# ultimatedrive2.net
KiCad netlist of a schematic drawn in EAGLE
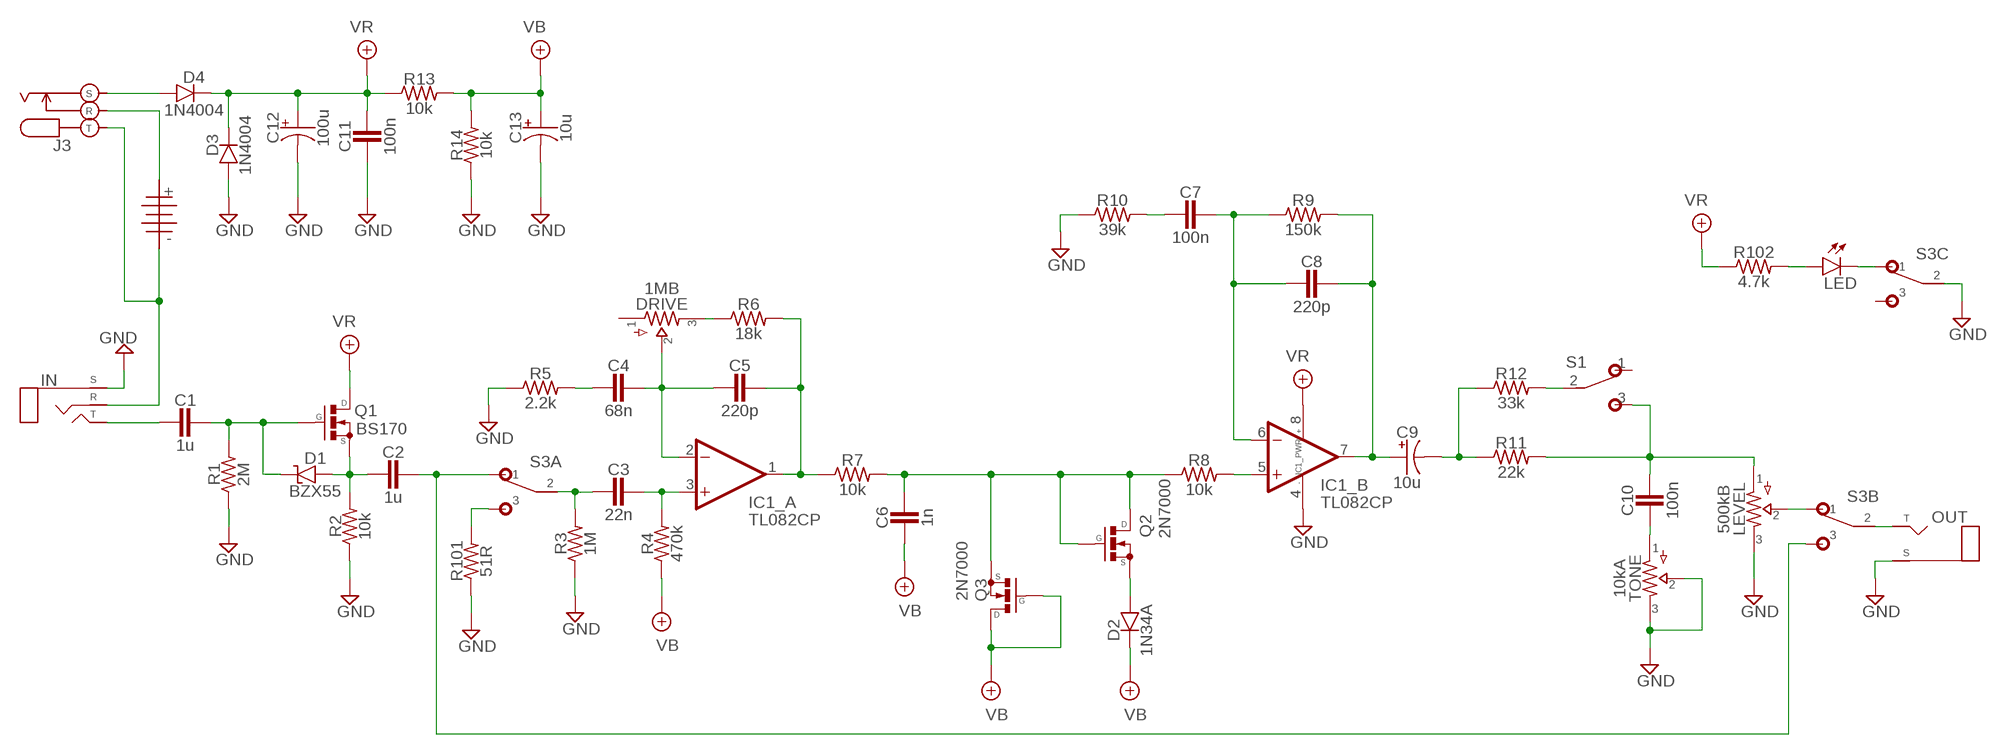
[diagram p0: schematic, sheet 1]

(export (version "E")
  (design (tool "Eeschema 10.0.6"))
  (components
    (comp (ref "1")
      (value "BATTERY")
      (footprint "eagle-import:TWO_PADS")
      (libsource (lib "eagle-import") (part "BATTERY"))
    )
    (comp (ref "C1")
      (value "1u")
      (footprint "eagle-import:BOX_SMALL")
      (libsource (lib "eagle-import") (part "CER/FILMBOX.1"))
    )
    (comp (ref "C2")
      (value "1u")
      (footprint "eagle-import:BOX_SMALL")
      (libsource (lib "eagle-import") (part "CER/FILMBOX.1"))
    )
    (comp (ref "C3")
      (value "22n")
      (footprint "eagle-import:BOX_SMALL")
      (libsource (lib "eagle-import") (part "CER/FILMBOX.1"))
    )
    (comp (ref "C4")
      (value "68n")
      (footprint "eagle-import:BOX_SMALL")
      (libsource (lib "eagle-import") (part "CER/FILMBOX.1"))
    )
    (comp (ref "C5")
      (value "220p")
      (footprint "eagle-import:BOX_SMALL")
      (libsource (lib "eagle-import") (part "CER/FILMBOX.1"))
    )
    (comp (ref "C6")
      (value "1n")
      (footprint "eagle-import:BOX_SMALL")
      (libsource (lib "eagle-import") (part "CER/FILMBOX.1"))
    )
    (comp (ref "C7")
      (value "100n")
      (footprint "eagle-import:BOX_SMALL")
      (libsource (lib "eagle-import") (part "CER/FILMBOX.1"))
    )
    (comp (ref "C8")
      (value "220p")
      (footprint "eagle-import:BOX_SMALL")
      (libsource (lib "eagle-import") (part "CER/FILMBOX.1"))
    )
    (comp (ref "C9")
      (value "10u")
      (footprint "eagle-import:050_020")
      (libsource (lib "eagle-import") (part "0500"))
    )
    (comp (ref "C10")
      (value "100n")
      (footprint "eagle-import:BOX_SMALL")
      (libsource (lib "eagle-import") (part "CER/FILMBOX.1"))
    )
    (comp (ref "C11")
      (value "100n")
      (footprint "eagle-import:BOX_SMALL")
      (libsource (lib "eagle-import") (part "CER/FILMBOX.1"))
    )
    (comp (ref "C12")
      (value "100u")
      (footprint "eagle-import:050_020")
      (libsource (lib "eagle-import") (part "0500"))
    )
    (comp (ref "C13")
      (value "10u")
      (footprint "eagle-import:050_020")
      (libsource (lib "eagle-import") (part "0500"))
    )
    (comp (ref "D1")
      (value "BZX55")
      (footprint "eagle-import:DO41-3")
      (libsource (lib "eagle-import") (part "ZENER.3"))
    )
    (comp (ref "D2")
      (value "1N34A")
      (footprint "eagle-import:DO41-2")
      (libsource (lib "eagle-import") (part "DO41.2"))
    )
    (comp (ref "D3")
      (value "1N4004")
      (footprint "eagle-import:DO41-3")
      (libsource (lib "eagle-import") (part "DO41.3"))
    )
    (comp (ref "D4")
      (value "1N4004")
      (footprint "eagle-import:DO41-3")
      (libsource (lib "eagle-import") (part "DO41.3"))
    )
    (comp (ref "DRIVE")
      (value "1MB")
      (footprint "eagle-import:16MM")
      (libsource (lib "eagle-import") (part "POTS16MM"))
    )
    (comp (ref "IC1")
      (value "TL082CP")
      (footprint "eagle-import:DIL0")
      (libsource (lib "eagle-import") (part "DUALTH"))
    )
    (comp (ref "IN")
      (value "STEREO")
      (footprint "eagle-import:STEREO_PCB")
      (libsource (lib "eagle-import") (part "STEREO"))
    )
    (comp (ref "J3")
      (value "DC_KOBICONN")
      (footprint "eagle-import:DC_KOBICONN")
      (libsource (lib "eagle-import") (part "DC_KOBICONN"))
    )
    (comp (ref "LED")
      (value "LED")
      (footprint "eagle-import:3MM_D")
      (libsource (lib "eagle-import") (part "LED"))
    )
    (comp (ref "LEVEL")
      (value "500kB")
      (footprint "eagle-import:16MM")
      (libsource (lib "eagle-import") (part "POTS16MM"))
    )
    (comp (ref "OUT")
      (value "MONO")
      (footprint "eagle-import:TWO_PADS")
      (libsource (lib "eagle-import") (part "MONO"))
    )
    (comp (ref "Q1")
      (value "BS170")
      (footprint "eagle-import:SOT54ES")
      (libsource (lib "eagle-import") (part "BS170"))
    )
    (comp (ref "Q2")
      (value "2N7000")
      (footprint "eagle-import:TO92-")
      (libsource (lib "eagle-import") (part "2N7000"))
    )
    (comp (ref "Q3")
      (value "2N7000")
      (footprint "eagle-import:TO92-")
      (libsource (lib "eagle-import") (part "2N7000"))
    )
    (comp (ref "R1")
      (value "2M")
      (footprint "eagle-import:R0207_3")
      (libsource (lib "eagle-import") (part "R_.3B"))
    )
    (comp (ref "R2")
      (value "10k")
      (footprint "eagle-import:R0207_3")
      (libsource (lib "eagle-import") (part "R_.3B"))
    )
    (comp (ref "R3")
      (value "1M")
      (footprint "eagle-import:R0207_3")
      (libsource (lib "eagle-import") (part "R_.3B"))
    )
    (comp (ref "R4")
      (value "470k")
      (footprint "eagle-import:R0207_3")
      (libsource (lib "eagle-import") (part "R_.3B"))
    )
    (comp (ref "R5")
      (value "2.2k")
      (footprint "eagle-import:R0207_3")
      (libsource (lib "eagle-import") (part "R_.3B"))
    )
    (comp (ref "R6")
      (value "18k")
      (footprint "eagle-import:R0207_3")
      (libsource (lib "eagle-import") (part "R_.3B"))
    )
    (comp (ref "R7")
      (value "10k")
      (footprint "eagle-import:R0207_3")
      (libsource (lib "eagle-import") (part "R_.3B"))
    )
    (comp (ref "R8")
      (value "10k")
      (footprint "eagle-import:R0207_3")
      (libsource (lib "eagle-import") (part "R_.3B"))
    )
    (comp (ref "R9")
      (value "150k")
      (footprint "eagle-import:R0207_3")
      (libsource (lib "eagle-import") (part "R_.3B"))
    )
    (comp (ref "R10")
      (value "39k")
      (footprint "eagle-import:R0207_3")
      (libsource (lib "eagle-import") (part "R_.3B"))
    )
    (comp (ref "R11")
      (value "22k")
      (footprint "eagle-import:R0207_3")
      (libsource (lib "eagle-import") (part "R_.3B"))
    )
    (comp (ref "R12")
      (value "33k")
      (footprint "eagle-import:R0207_3")
      (libsource (lib "eagle-import") (part "R_.3B"))
    )
    (comp (ref "R13")
      (value "10k")
      (footprint "eagle-import:R0207_3")
      (libsource (lib "eagle-import") (part "R_.3B"))
    )
    (comp (ref "R14")
      (value "10k")
      (footprint "eagle-import:R0207_3")
      (libsource (lib "eagle-import") (part "R_.3B"))
    )
    (comp (ref "R101")
      (value "51R")
      (footprint "eagle-import:R0207_3")
      (libsource (lib "eagle-import") (part "R_.3B"))
    )
    (comp (ref "R102")
      (value "4.7k")
      (footprint "eagle-import:R0207_3")
      (libsource (lib "eagle-import") (part "R_.3B"))
    )
    (comp (ref "S1")
      (value "SPDT")
      (footprint "eagle-import:M9040P")
      (libsource (lib "eagle-import") (part "SPDT"))
    )
    (comp (ref "S3")
      (value "3PDT")
      (footprint "eagle-import:3PDT")
      (libsource (lib "eagle-import") (part "3PDT"))
    )
    (comp (ref "TONE")
      (value "10kA")
      (footprint "eagle-import:16MM")
      (libsource (lib "eagle-import") (part "POTS16MM"))
    )
  )
  (nets
    (net (code "1") (name "GND") (class "Default")
      (node (ref "C11") (pin "2") (pinfunction "2_2") (pintype "passive"))
      (node (ref "C12") (pin "-") (pinfunction "-_-") (pintype "passive"))
      (node (ref "C13") (pin "-") (pinfunction "-_-") (pintype "passive"))
      (node (ref "D3") (pin "A") (pinfunction "A_A") (pintype "passive"))
      (node (ref "IC1") (pin "4") (pinfunction "V-_4") (pintype "power_in"))
      (node (ref "IN") (pin "P$1") (pinfunction "S_P$1") (pintype "passive"))
      (node (ref "LEVEL") (pin "3") (pinfunction "3_3") (pintype "passive"))
      (node (ref "OUT") (pin "S") (pinfunction "SLEEVE_S") (pintype "passive"))
      (node (ref "R1") (pin "1") (pinfunction "1_1") (pintype "passive"))
      (node (ref "R10") (pin "1") (pinfunction "1_1") (pintype "passive"))
      (node (ref "R101") (pin "1") (pinfunction "1_1") (pintype "passive"))
      (node (ref "R14") (pin "1") (pinfunction "1_1") (pintype "passive"))
      (node (ref "R2") (pin "1") (pinfunction "1_1") (pintype "passive"))
      (node (ref "R3") (pin "1") (pinfunction "1_1") (pintype "passive"))
      (node (ref "R5") (pin "1") (pinfunction "1_1") (pintype "passive"))
      (node (ref "S3") (pin "C2") (pinfunction "2_C2") (pintype "passive"))
      (node (ref "TONE") (pin "2") (pinfunction "2_2") (pintype "passive"))
      (node (ref "TONE") (pin "3") (pinfunction "3_3") (pintype "passive"))
    )
    (net (code "2") (name "Net-(1-P$1)") (class "Default")
      (node (ref "1") (pin "T") (pinfunction "P$1_T") (pintype "bidirectional"))
      (node (ref "J3") (pin "R") (pinfunction "R_R") (pintype "bidirectional"))
    )
    (net (code "3") (name "Net-(1-P$2)") (class "Default")
      (node (ref "1") (pin "S") (pinfunction "P$2_S") (pintype "bidirectional"))
      (node (ref "IN") (pin "P$2") (pinfunction "R_P$2") (pintype "passive"))
      (node (ref "J3") (pin "T") (pinfunction "T_T") (pintype "bidirectional"))
    )
    (net (code "4") (name "Net-(C1-Pad1)") (class "Default")
      (node (ref "C1") (pin "1") (pinfunction "1_1") (pintype "passive"))
      (node (ref "D1") (pin "C") (pinfunction "C_C") (pintype "passive"))
      (node (ref "Q1") (pin "G") (pinfunction "G_G") (pintype "passive"))
      (node (ref "R1") (pin "2") (pinfunction "2_2") (pintype "passive"))
    )
    (net (code "5") (name "Net-(C2-Pad2)") (class "Default")
      (node (ref "C2") (pin "2") (pinfunction "2_2") (pintype "passive"))
      (node (ref "D1") (pin "A") (pinfunction "A_A") (pintype "passive"))
      (node (ref "Q1") (pin "S") (pinfunction "S_S") (pintype "passive"))
      (node (ref "R2") (pin "2") (pinfunction "2_2") (pintype "passive"))
    )
    (net (code "6") (name "Net-(C4-Pad2)") (class "Default")
      (node (ref "C4") (pin "2") (pinfunction "2_2") (pintype "passive"))
      (node (ref "R5") (pin "2") (pinfunction "2_2") (pintype "passive"))
    )
    (net (code "7") (name "Net-(C7-Pad2)") (class "Default")
      (node (ref "C7") (pin "2") (pinfunction "2_2") (pintype "passive"))
      (node (ref "R10") (pin "2") (pinfunction "2_2") (pintype "passive"))
    )
    (net (code "8") (name "Net-(C9-Pad-)") (class "Default")
      (node (ref "C9") (pin "-") (pinfunction "-_-") (pintype "passive"))
      (node (ref "R11") (pin "1") (pinfunction "1_1") (pintype "passive"))
      (node (ref "R12") (pin "1") (pinfunction "1_1") (pintype "passive"))
    )
    (net (code "9") (name "Net-(C10-Pad2)") (class "Default")
      (node (ref "C10") (pin "2") (pinfunction "2_2") (pintype "passive"))
      (node (ref "TONE") (pin "1") (pinfunction "1_1") (pintype "passive"))
    )
    (net (code "10") (name "Net-(D4-PadA)") (class "Default")
      (node (ref "D4") (pin "A") (pinfunction "A_A") (pintype "passive"))
      (node (ref "J3") (pin "S") (pinfunction "S_S") (pintype "bidirectional"))
    )
    (net (code "11") (name "Net-(DRIVE-Pad3)") (class "Default")
      (node (ref "DRIVE") (pin "3") (pinfunction "3_3") (pintype "passive"))
      (node (ref "R6") (pin "1") (pinfunction "1_1") (pintype "passive"))
    )
    (net (code "12") (name "Net-(IC1A-+IN)") (class "Default")
      (node (ref "C3") (pin "1") (pinfunction "1_1") (pintype "passive"))
      (node (ref "IC1") (pin "3") (pinfunction "+IN_3") (pintype "input"))
      (node (ref "R4") (pin "2") (pinfunction "2_2") (pintype "passive"))
    )
    (net (code "13") (name "Net-(IC1A--IN)") (class "Default")
      (node (ref "C4") (pin "1") (pinfunction "1_1") (pintype "passive"))
      (node (ref "C5") (pin "2") (pinfunction "2_2") (pintype "passive"))
      (node (ref "DRIVE") (pin "2") (pinfunction "2_2") (pintype "passive"))
      (node (ref "IC1") (pin "2") (pinfunction "-IN_2") (pintype "input"))
    )
    (net (code "14") (name "Net-(IC1A-OUT)") (class "Default")
      (node (ref "C5") (pin "1") (pinfunction "1_1") (pintype "passive"))
      (node (ref "IC1") (pin "1") (pinfunction "OUT_1") (pintype "output"))
      (node (ref "R6") (pin "2") (pinfunction "2_2") (pintype "passive"))
      (node (ref "R7") (pin "1") (pinfunction "1_1") (pintype "passive"))
    )
    (net (code "15") (name "Net-(IC1B-+IN)") (class "Default")
      (node (ref "IC1") (pin "5") (pinfunction "+IN_5") (pintype "input"))
      (node (ref "R8") (pin "2") (pinfunction "2_2") (pintype "passive"))
    )
    (net (code "16") (name "Net-(IC1B--IN)") (class "Default")
      (node (ref "C7") (pin "1") (pinfunction "1_1") (pintype "passive"))
      (node (ref "C8") (pin "2") (pinfunction "2_2") (pintype "passive"))
      (node (ref "IC1") (pin "6") (pinfunction "-IN_6") (pintype "input"))
      (node (ref "R9") (pin "1") (pinfunction "1_1") (pintype "passive"))
    )
    (net (code "17") (name "Net-(IC1B-OUT)") (class "Default")
      (node (ref "C8") (pin "1") (pinfunction "1_1") (pintype "passive"))
      (node (ref "C9") (pin "+") (pinfunction "+_+") (pintype "passive"))
      (node (ref "IC1") (pin "7") (pinfunction "OUT_7") (pintype "output"))
      (node (ref "R9") (pin "2") (pinfunction "2_2") (pintype "passive"))
    )
    (net (code "18") (name "Net-(IN-T)") (class "Default")
      (node (ref "C1") (pin "2") (pinfunction "2_2") (pintype "passive"))
      (node (ref "IN") (pin "P$3") (pinfunction "T_P$3") (pintype "passive"))
    )
    (net (code "19") (name "Net-(LED-A)") (class "Default")
      (node (ref "LED") (pin "ANODE") (pinfunction "A_ANODE") (pintype "passive"))
      (node (ref "R102") (pin "2") (pinfunction "2_2") (pintype "passive"))
    )
    (net (code "20") (name "Net-(LED-C)") (class "Default")
      (node (ref "LED") (pin "P$1") (pinfunction "C_P$1") (pintype "passive"))
      (node (ref "S3") (pin "C1") (pinfunction "1_C1") (pintype "passive"))
    )
    (net (code "21") (name "Net-(OUT-TIP)") (class "Default")
      (node (ref "OUT") (pin "T") (pinfunction "TIP_T") (pintype "passive"))
      (node (ref "S3") (pin "B2") (pinfunction "2_B2") (pintype "passive"))
    )
    (net (code "22") (name "Net-(Q2-D)") (class "Default")
      (node (ref "C6") (pin "1") (pinfunction "1_1") (pintype "passive"))
      (node (ref "Q2") (pin "1") (pinfunction "D_1") (pintype "passive"))
      (node (ref "Q2") (pin "2") (pinfunction "G_2") (pintype "passive"))
      (node (ref "Q3") (pin "3") (pinfunction "S_3") (pintype "passive"))
      (node (ref "R7") (pin "2") (pinfunction "2_2") (pintype "passive"))
      (node (ref "R8") (pin "1") (pinfunction "1_1") (pintype "passive"))
    )
    (net (code "23") (name "Net-(Q2-S)") (class "Default")
      (node (ref "D2") (pin "A") (pinfunction "A_A") (pintype "passive"))
      (node (ref "Q2") (pin "3") (pinfunction "S_3") (pintype "passive"))
    )
    (net (code "24") (name "Net-(S1-P)") (class "Default")
      (node (ref "R12") (pin "2") (pinfunction "2_2") (pintype "passive"))
      (node (ref "S1") (pin "2") (pinfunction "P_2") (pintype "passive"))
    )
    (net (code "25") (name "Net-(S1-S)") (class "Default")
      (node (ref "C10") (pin "1") (pinfunction "1_1") (pintype "passive"))
      (node (ref "LEVEL") (pin "1") (pinfunction "1_1") (pintype "passive"))
      (node (ref "R11") (pin "2") (pinfunction "2_2") (pintype "passive"))
      (node (ref "S1") (pin "3") (pinfunction "S_3") (pintype "passive"))
    )
    (net (code "26") (name "Net-(S3A-1)") (class "Default")
      (node (ref "C2") (pin "1") (pinfunction "1_1") (pintype "passive"))
      (node (ref "S3") (pin "A1") (pinfunction "1_A1") (pintype "passive"))
      (node (ref "S3") (pin "B3") (pinfunction "3_B3") (pintype "passive"))
    )
    (net (code "27") (name "Net-(S3A-2)") (class "Default")
      (node (ref "C3") (pin "2") (pinfunction "2_2") (pintype "passive"))
      (node (ref "R3") (pin "2") (pinfunction "2_2") (pintype "passive"))
      (node (ref "S3") (pin "A2") (pinfunction "2_A2") (pintype "passive"))
    )
    (net (code "28") (name "Net-(S3A-3)") (class "Default")
      (node (ref "R101") (pin "2") (pinfunction "2_2") (pintype "passive"))
      (node (ref "S3") (pin "A3") (pinfunction "3_A3") (pintype "passive"))
    )
    (net (code "29") (name "Net-(S3B-1)") (class "Default")
      (node (ref "LEVEL") (pin "2") (pinfunction "2_2") (pintype "passive"))
      (node (ref "S3") (pin "B1") (pinfunction "1_B1") (pintype "passive"))
    )
    (net (code "30") (name "VB") (class "Default")
      (node (ref "C13") (pin "+") (pinfunction "+_+") (pintype "passive"))
      (node (ref "C6") (pin "2") (pinfunction "2_2") (pintype "passive"))
      (node (ref "D2") (pin "C") (pinfunction "C_C") (pintype "passive"))
      (node (ref "Q3") (pin "1") (pinfunction "D_1") (pintype "passive"))
      (node (ref "Q3") (pin "2") (pinfunction "G_2") (pintype "passive"))
      (node (ref "R13") (pin "2") (pinfunction "2_2") (pintype "passive"))
      (node (ref "R14") (pin "2") (pinfunction "2_2") (pintype "passive"))
      (node (ref "R4") (pin "1") (pinfunction "1_1") (pintype "passive"))
    )
    (net (code "31") (name "VR") (class "Default")
      (node (ref "C11") (pin "1") (pinfunction "1_1") (pintype "passive"))
      (node (ref "C12") (pin "+") (pinfunction "+_+") (pintype "passive"))
      (node (ref "D3") (pin "C") (pinfunction "C_C") (pintype "passive"))
      (node (ref "D4") (pin "C") (pinfunction "C_C") (pintype "passive"))
      (node (ref "IC1") (pin "8") (pinfunction "V+_8") (pintype "power_in"))
      (node (ref "Q1") (pin "D") (pinfunction "D_D") (pintype "passive"))
      (node (ref "R102") (pin "1") (pinfunction "1_1") (pintype "passive"))
      (node (ref "R13") (pin "1") (pinfunction "1_1") (pintype "passive"))
    )
    (net (code "32") (name "unconnected-(DRIVE-Pad1)") (class "Default")
      (node (ref "DRIVE") (pin "1") (pinfunction "1_1") (pintype "passive"))
    )
    (net (code "33") (name "unconnected-(S1-O-Pad1)") (class "Default")
      (node (ref "S1") (pin "1") (pinfunction "O_1") (pintype "passive"))
    )
    (net (code "34") (name "unconnected-(S3C-3-PadC3)") (class "Default")
      (node (ref "S3") (pin "C3") (pinfunction "3_C3") (pintype "passive"))
    )
  )
)
